# 1-3.net
KiCad netlist of a schematic drawn in EAGLE
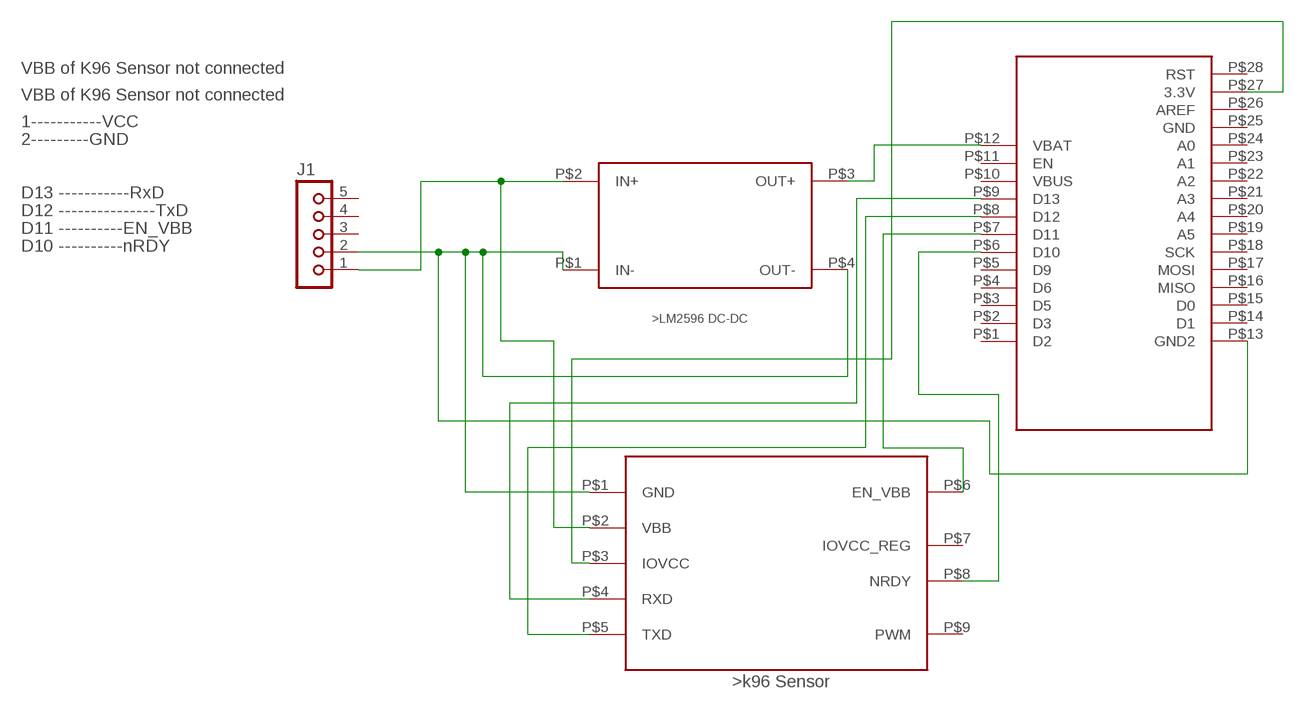
[diagram p0: schematic, sheet 1]

(export (version "E")
  (design (tool "Eeschema 10.0.6"))
  (components
    (comp (ref "DCDC1")
      (value "DCDC")
      (footprint "eagle-import:DCDC")
      (libsource (lib "eagle-import") (part "DCDC"))
    )
    (comp (ref "FEATHER1")
      (value "FEATHER")
      (footprint "eagle-import:FEATHER")
      (libsource (lib "eagle-import") (part "FEATHER"))
    )
    (comp (ref "J1")
      (value "JU05")
      (footprint "eagle-import:JU05")
      (libsource (lib "eagle-import") (part "JU05"))
    )
    (comp (ref "K96SENSOR1")
      (value "K96SENSOR")
      (footprint "eagle-import:K96SENSOR")
      (libsource (lib "eagle-import") (part "K96SENSOR"))
    )
  )
  (nets
    (net (code "1") (name "Net-(DCDC1-IN+)") (class "Default")
      (node (ref "DCDC1") (pin "P$2") (pinfunction "IN+_P$2") (pintype "bidirectional"))
      (node (ref "J1") (pin "1") (pinfunction "1_1") (pintype "passive"))
      (node (ref "K96SENSOR1") (pin "P$2") (pinfunction "VBB_P$2") (pintype "bidirectional"))
    )
    (net (code "2") (name "Net-(DCDC1-IN-)") (class "Default")
      (node (ref "DCDC1") (pin "P$1") (pinfunction "IN-_P$1") (pintype "bidirectional"))
      (node (ref "DCDC1") (pin "P$4") (pinfunction "OUT-_P$4") (pintype "bidirectional"))
      (node (ref "FEATHER1") (pin "P$13") (pinfunction "GND2_P$13") (pintype "bidirectional"))
      (node (ref "J1") (pin "2") (pinfunction "2_2") (pintype "passive"))
      (node (ref "K96SENSOR1") (pin "P$1") (pinfunction "GND_P$1") (pintype "bidirectional"))
    )
    (net (code "3") (name "Net-(DCDC1-OUT+)") (class "Default")
      (node (ref "DCDC1") (pin "P$3") (pinfunction "OUT+_P$3") (pintype "bidirectional"))
      (node (ref "FEATHER1") (pin "P$12") (pinfunction "VBAT_P$12") (pintype "bidirectional"))
    )
    (net (code "4") (name "Net-(FEATHER1-3.3V)") (class "Default")
      (node (ref "FEATHER1") (pin "P$27") (pinfunction "3.3V_P$27") (pintype "bidirectional"))
      (node (ref "K96SENSOR1") (pin "P$3") (pinfunction "IOVCC_P$3") (pintype "bidirectional"))
    )
    (net (code "5") (name "Net-(FEATHER1-D10)") (class "Default")
      (node (ref "FEATHER1") (pin "P$6") (pinfunction "D10_P$6") (pintype "bidirectional"))
      (node (ref "K96SENSOR1") (pin "P$8") (pinfunction "NRDY_P$8") (pintype "bidirectional"))
    )
    (net (code "6") (name "Net-(FEATHER1-D11)") (class "Default")
      (node (ref "FEATHER1") (pin "P$7") (pinfunction "D11_P$7") (pintype "bidirectional"))
      (node (ref "K96SENSOR1") (pin "P$6") (pinfunction "EN_VBB_P$6") (pintype "bidirectional"))
    )
    (net (code "7") (name "Net-(FEATHER1-D12)") (class "Default")
      (node (ref "FEATHER1") (pin "P$8") (pinfunction "D12_P$8") (pintype "bidirectional"))
      (node (ref "K96SENSOR1") (pin "P$5") (pinfunction "TXD_P$5") (pintype "bidirectional"))
    )
    (net (code "8") (name "Net-(FEATHER1-D13)") (class "Default")
      (node (ref "FEATHER1") (pin "P$9") (pinfunction "D13_P$9") (pintype "bidirectional"))
      (node (ref "K96SENSOR1") (pin "P$4") (pinfunction "RXD_P$4") (pintype "bidirectional"))
    )
    (net (code "9") (name "unconnected-(FEATHER1-A0-PadP$24)") (class "Default")
      (node (ref "FEATHER1") (pin "P$24") (pinfunction "A0_P$24") (pintype "bidirectional"))
    )
    (net (code "10") (name "unconnected-(FEATHER1-A1-PadP$23)") (class "Default")
      (node (ref "FEATHER1") (pin "P$23") (pinfunction "A1_P$23") (pintype "bidirectional"))
    )
    (net (code "11") (name "unconnected-(FEATHER1-A2-PadP$22)") (class "Default")
      (node (ref "FEATHER1") (pin "P$22") (pinfunction "A2_P$22") (pintype "bidirectional"))
    )
    (net (code "12") (name "unconnected-(FEATHER1-A3-PadP$21)") (class "Default")
      (node (ref "FEATHER1") (pin "P$21") (pinfunction "A3_P$21") (pintype "bidirectional"))
    )
    (net (code "13") (name "unconnected-(FEATHER1-A4-PadP$20)") (class "Default")
      (node (ref "FEATHER1") (pin "P$20") (pinfunction "A4_P$20") (pintype "bidirectional"))
    )
    (net (code "14") (name "unconnected-(FEATHER1-A5-PadP$19)") (class "Default")
      (node (ref "FEATHER1") (pin "P$19") (pinfunction "A5_P$19") (pintype "bidirectional"))
    )
    (net (code "15") (name "unconnected-(FEATHER1-AREF-PadP$26)") (class "Default")
      (node (ref "FEATHER1") (pin "P$26") (pinfunction "AREF_P$26") (pintype "bidirectional"))
    )
    (net (code "16") (name "unconnected-(FEATHER1-D0-PadP$15)") (class "Default")
      (node (ref "FEATHER1") (pin "P$15") (pinfunction "D0_P$15") (pintype "bidirectional"))
    )
    (net (code "17") (name "unconnected-(FEATHER1-D1-PadP$14)") (class "Default")
      (node (ref "FEATHER1") (pin "P$14") (pinfunction "D1_P$14") (pintype "bidirectional"))
    )
    (net (code "18") (name "unconnected-(FEATHER1-D2-PadP$1)") (class "Default")
      (node (ref "FEATHER1") (pin "P$1") (pinfunction "D2_P$1") (pintype "bidirectional"))
    )
    (net (code "19") (name "unconnected-(FEATHER1-D3-PadP$2)") (class "Default")
      (node (ref "FEATHER1") (pin "P$2") (pinfunction "D3_P$2") (pintype "bidirectional"))
    )
    (net (code "20") (name "unconnected-(FEATHER1-D5-PadP$3)") (class "Default")
      (node (ref "FEATHER1") (pin "P$3") (pinfunction "D5_P$3") (pintype "bidirectional"))
    )
    (net (code "21") (name "unconnected-(FEATHER1-D6-PadP$4)") (class "Default")
      (node (ref "FEATHER1") (pin "P$4") (pinfunction "D6_P$4") (pintype "bidirectional"))
    )
    (net (code "22") (name "unconnected-(FEATHER1-D9-PadP$5)") (class "Default")
      (node (ref "FEATHER1") (pin "P$5") (pinfunction "D9_P$5") (pintype "bidirectional"))
    )
    (net (code "23") (name "unconnected-(FEATHER1-EN-PadP$11)") (class "Default")
      (node (ref "FEATHER1") (pin "P$11") (pinfunction "EN_P$11") (pintype "bidirectional"))
    )
    (net (code "24") (name "unconnected-(FEATHER1-GND-PadP$25)") (class "Default")
      (node (ref "FEATHER1") (pin "P$25") (pinfunction "GND_P$25") (pintype "bidirectional"))
    )
    (net (code "25") (name "unconnected-(FEATHER1-MISO-PadP$16)") (class "Default")
      (node (ref "FEATHER1") (pin "P$16") (pinfunction "MISO_P$16") (pintype "bidirectional"))
    )
    (net (code "26") (name "unconnected-(FEATHER1-MOSI-PadP$17)") (class "Default")
      (node (ref "FEATHER1") (pin "P$17") (pinfunction "MOSI_P$17") (pintype "bidirectional"))
    )
    (net (code "27") (name "unconnected-(FEATHER1-RST-PadP$28)") (class "Default")
      (node (ref "FEATHER1") (pin "P$28") (pinfunction "RST_P$28") (pintype "bidirectional"))
    )
    (net (code "28") (name "unconnected-(FEATHER1-SCK-PadP$18)") (class "Default")
      (node (ref "FEATHER1") (pin "P$18") (pinfunction "SCK_P$18") (pintype "bidirectional"))
    )
    (net (code "29") (name "unconnected-(FEATHER1-VBUS-PadP$10)") (class "Default")
      (node (ref "FEATHER1") (pin "P$10") (pinfunction "VBUS_P$10") (pintype "bidirectional"))
    )
    (net (code "30") (name "unconnected-(J1-Pad3)") (class "Default")
      (node (ref "J1") (pin "3") (pinfunction "3_3") (pintype "passive"))
    )
    (net (code "31") (name "unconnected-(J1-Pad4)") (class "Default")
      (node (ref "J1") (pin "4") (pinfunction "4_4") (pintype "passive"))
    )
    (net (code "32") (name "unconnected-(J1-Pad5)") (class "Default")
      (node (ref "J1") (pin "5") (pinfunction "5_5") (pintype "passive"))
    )
    (net (code "33") (name "unconnected-(K96SENSOR1-IOVCC_REG-PadP$7)") (class "Default")
      (node (ref "K96SENSOR1") (pin "P$7") (pinfunction "IOVCC_REG_P$7") (pintype "bidirectional"))
    )
    (net (code "34") (name "unconnected-(K96SENSOR1-PWM-PadP$9)") (class "Default")
      (node (ref "K96SENSOR1") (pin "P$9") (pinfunction "PWM_P$9") (pintype "bidirectional"))
    )
  )
)
